# RAK3162_NRF54L15.net
KiCad netlist of a schematic drawn in Altium Designer
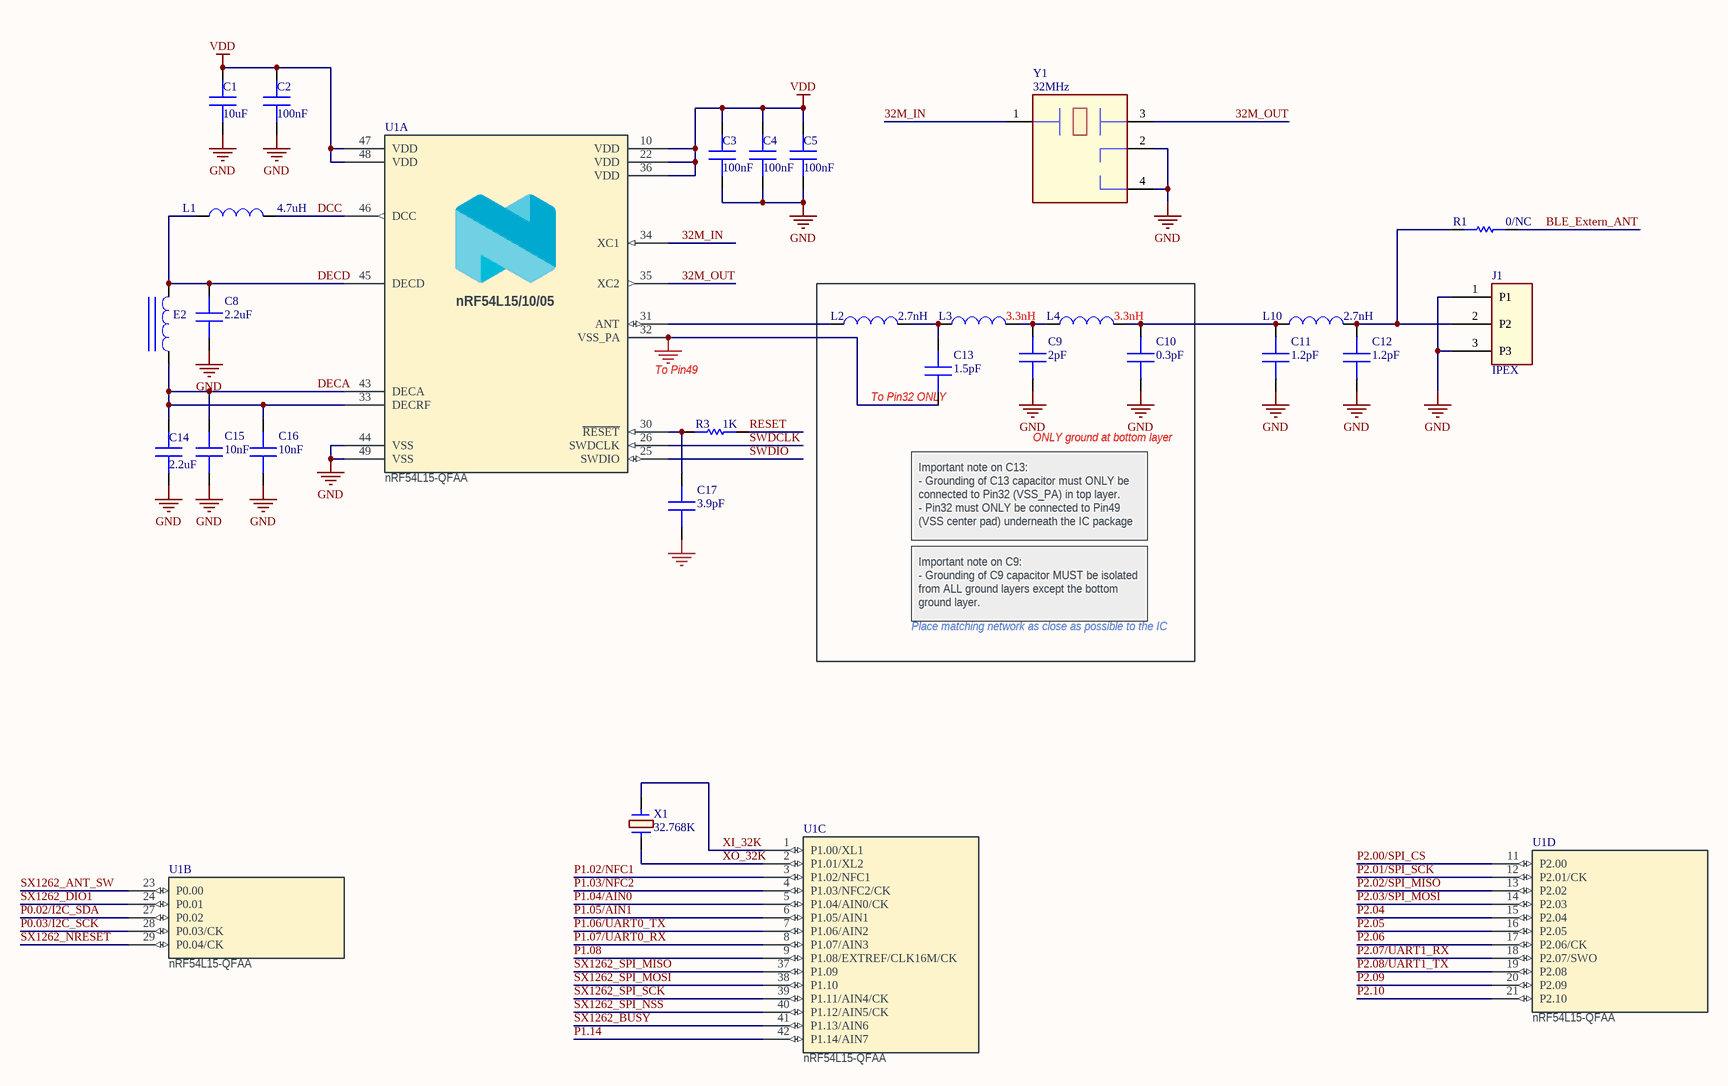
[diagram p0: RAK3162_NRF54L15.SchDoc]

(export (version "E")
  (design (tool "Eeschema 10.0.6"))
  (components
    (comp (ref "C1")
      (value "10uF")
      (footprint "sc0402")
      (description "Capacitor-10V-10uF-±20%-X5R-0402")
      (fields (field (name "MANUFACTURER") "YAGEO") (field (name "TOLERANCE") "±20%"))
      (libsource (lib "RAK_Database_Lib_2022") (part "CAPACITOR NP"))
    )
    (comp (ref "C2")
      (value "100nF")
      (footprint "sc0201")
      (description "Capacitor-6.3V-100nF-±10%-X5R-0201")
      (fields (field (name "MANUFACTURER") "YAGEO") (field (name "TOLERANCE") "±10%"))
      (libsource (lib "RAK_Database_Lib_2022") (part "CAPACITOR NP"))
    )
    (comp (ref "C3")
      (value "100nF")
      (footprint "sc0201")
      (description "Capacitor-6.3V-100nF-±10%-X5R-0201")
      (fields (field (name "MANUFACTURER") "YAGEO") (field (name "TOLERANCE") "±10%"))
      (libsource (lib "RAK_Database_Lib_2022") (part "CAPACITOR NP"))
    )
    (comp (ref "C4")
      (value "100nF")
      (footprint "sc0201")
      (description "Capacitor-6.3V-100nF-±10%-X5R-0201")
      (fields (field (name "MANUFACTURER") "YAGEO") (field (name "TOLERANCE") "±10%"))
      (libsource (lib "RAK_Database_Lib_2022") (part "CAPACITOR NP"))
    )
    (comp (ref "C5")
      (value "100nF")
      (footprint "sc0201")
      (description "Capacitor-6.3V-100nF-±10%-X5R-0201")
      (fields (field (name "MANUFACTURER") "YAGEO") (field (name "TOLERANCE") "±10%"))
      (libsource (lib "RAK_Database_Lib_2022") (part "CAPACITOR NP"))
    )
    (comp (ref "C8")
      (value "2.2uF")
      (footprint "sc0201")
      (description "Capacitor-6.3V-2.2uF-±20%-X5R-0201")
      (fields (field (name "MANUFACTURER") "YAGEO") (field (name "TOLERANCE") "±20%"))
      (libsource (lib "RAK_Database_Lib_2022") (part "CAPACITOR NP"))
    )
    (comp (ref "C9")
      (value "2pF")
      (footprint "sc0201")
      (description "Capacitor-50V-2pF-±0.1pF-COG-0201")
      (fields (field (name "MANUFACTURER") "深圳市宇阳科技发展有限公司") (field (name "TOLERANCE") "±0.1pF"))
      (libsource (lib "RAK_Database_Lib_2022") (part "CAPACITOR NP"))
    )
    (comp (ref "C10")
      (value "0.3pF")
      (footprint "sc0201")
      (description "Capacitor-50V-0.3pF-±0.1pF-NPO-0201")
      (fields (field (name "MANUFACTURER") "YAGEO") (field (name "TOLERANCE") "±0.1pF"))
      (libsource (lib "RAK_Database_Lib_2022") (part "CAPACITOR NP"))
    )
    (comp (ref "C11")
      (value "1.2pF")
      (footprint "sc0201")
      (description "Capacitor-50V-1.2pF-±0.1pF-COG-0201")
      (fields (field (name "MANUFACTURER") "MuRATA") (field (name "TOLERANCE") "±0.1pF"))
      (libsource (lib "RAK_Database_Lib_2022") (part "CAPACITOR NP"))
    )
    (comp (ref "C12")
      (value "1.2pF")
      (footprint "sc0201")
      (description "Capacitor-50V-1.2pF-±0.1pF-COG-0201")
      (fields (field (name "MANUFACTURER") "MuRATA") (field (name "TOLERANCE") "±0.1pF"))
      (libsource (lib "RAK_Database_Lib_2022") (part "CAPACITOR NP"))
    )
    (comp (ref "C13")
      (value "1.5pF")
      (footprint "sc0201")
      (description "Capacitor-50V-1.5pF-±0.25pF-COG-0201")
      (fields (field (name "MANUFACTURER") "YAGEO") (field (name "TOLERANCE") "±0.25pF"))
      (libsource (lib "RAK_Database_Lib_2022") (part "CAPACITOR NP"))
    )
    (comp (ref "C14")
      (value "2.2uF")
      (footprint "sc0201")
      (description "Capacitor-6.3V-2.2uF-±20%-X5R-0201")
      (fields (field (name "MANUFACTURER") "YAGEO") (field (name "TOLERANCE") "±20%"))
      (libsource (lib "RAK_Database_Lib_2022") (part "CAPACITOR NP"))
    )
    (comp (ref "C15")
      (value "10nF")
      (footprint "sc0201")
      (description "Capacitor-10V-10nF-±10%-X7R-0201")
      (fields (field (name "MANUFACTURER") "YAGEO") (field (name "TOLERANCE") "±10%"))
      (libsource (lib "RAK_Database_Lib_2022") (part "CAPACITOR NP"))
    )
    (comp (ref "C16")
      (value "10nF")
      (footprint "sc0201")
      (description "Capacitor-10V-10nF-±10%-X7R-0201")
      (fields (field (name "MANUFACTURER") "YAGEO") (field (name "TOLERANCE") "±10%"))
      (libsource (lib "RAK_Database_Lib_2022") (part "CAPACITOR NP"))
    )
    (comp (ref "C17")
      (value "3.9pF")
      (footprint "sc0201")
      (description "Capacitor-50V-3.9pF-±0.25pF-NPO-0201")
      (fields (field (name "MANUFACTURER") "YAGEO") (field (name "TOLERANCE") "±0.25pF"))
      (libsource (lib "RAK_Database_Lib_2022") (part "CAPACITOR NP"))
    )
    (comp (ref "E2")
      (value "BEAD")
      (footprint "SL0201")
      (description "EMI Ferrite Bead-240Ω±25%@100MHz-0.38Ω-350mA-0201")
      (fields (field (name "MANUFACTURER") "Murata") (field (name "PART NUMBER") "BLM03AX241SN1D"))
      (libsource (lib "RAK_Database_Lib_2022") (part "BEAD"))
    )
    (comp (ref "J1")
      (value "IPEX")
      (footprint "SCOXSMA_T")
      (description "Coaxial Connectors-IPEX MHF1-Receptacle, Male Pin-50Ohm-Surface Mount")
      (fields (field (name "MANUFACTURER") "BLDZ01") (field (name "PART_NUMBER") "ECT818000071"))
      (libsource (lib "RAK_Database_Lib_2022") (part "UFL"))
    )
    (comp (ref "L1")
      (value "4.7uH")
      (footprint "SL0603")
      (description "Power Inductor-4.7uH-±20%-0.5Ω-120mA-0603")
      (fields (field (name "MANUFACTURER") "TDK") (field (name "PART NUMBER") "MLZ1608M4R7WT000"))
      (libsource (lib "RAK_Database_Lib_2022") (part "INDUCTOR"))
    )
    (comp (ref "L2")
      (value "2.7nH")
      (footprint "sl0201")
      (description "Inductor-2.7nH-±0.1nH-0.2Ω-500mA-0201")
      (fields (field (name "MANUFACTURER") "MURATA") (field (name "PART NUMBER") "LQP03TN2N7B02D"))
      (libsource (lib "RAK_Database_Lib_2022") (part "INDUCTOR"))
    )
    (comp (ref "L3")
      (value "3.3nH")
      (footprint "sl0201")
      (description "Inductor-3.3nH-±0.1nH-0.25Ω-450mA-0201")
      (fields (field (name "MANUFACTURER") "MURATA") (field (name "PART NUMBER") "LQP03TN3N3B02"))
      (libsource (lib "RAK_Database_Lib_2022") (part "INDUCTOR"))
    )
    (comp (ref "L4")
      (value "3.3nH")
      (footprint "sl0201")
      (description "Inductor-3.3nH-±0.1nH-0.25Ω-450mA-0201")
      (fields (field (name "MANUFACTURER") "MURATA") (field (name "PART NUMBER") "LQP03TN3N3B02"))
      (libsource (lib "RAK_Database_Lib_2022") (part "INDUCTOR"))
    )
    (comp (ref "L10")
      (value "2.7nH")
      (footprint "sl0201")
      (description "Inductor-2.7nH-±0.1nH-0.2Ω-500mA-0201")
      (fields (field (name "MANUFACTURER") "MURATA") (field (name "PART NUMBER") "LQP03TN2N7B02D"))
      (libsource (lib "RAK_Database_Lib_2022") (part "INDUCTOR"))
    )
    (comp (ref "R1")
      (value "0/NC")
      (footprint "sr0201")
      (description "Resistor-0Ω-0.5A-50mΩMAX-0201")
      (fields (field (name "MANUFACTURER") "YAGEO") (field (name "PART NUMBER") "RC0201JR-070RL"))
      (libsource (lib "RAK_Database_Lib_2022") (part "RESISTOR"))
    )
    (comp (ref "R3")
      (value "1K")
      (footprint "sr0201")
      (description "Resistor-1/20W-1KΩ-±1%-0201")
      (fields (field (name "MANUFACTURER") "YAGEO") (field (name "PART NUMBER") "RC0201FR-071KL"))
      (libsource (lib "RAK_Database_Lib_2022") (part "RESISTOR"))
    )
    (comp (ref "U1")
      (value "nRF54L15-QFAA")
      (footprint "QFN40P600X600X90-48N")
      (fields (field (name "MANUFACTURER") "Nordic Semiconductor") (field (name "AUTHOR") "stl1"))
      (libsource (lib "RAK_Symbol_Library") (part "nRF54L15-QFAA"))
    )
    (comp (ref "X1")
      (value "32.768K")
      (footprint "CM212H")
      (description "Crystal-32.768KHz-12.5pF-±20ppm-−40~+85℃-SMD-2012-2pin")
      (fields (field (name "MANUFACTURER") "XTCS01") (field (name "PART NUMBER") "CM212H"))
      (libsource (lib "RAK_Database_Lib_2022") (part "CM212H"))
    )
    (comp (ref "Y1")
      (value "32MHz")
      (footprint "S0SC4-2016")
      (description "Crystal-32MHz-6pF-±20ppm-70Ω-SMD-2016-4pin")
      (fields (field (name "MANUFACTURER") "MURATA") (field (name "PART NUMBER") "XRCGB32M000F2P10R0"))
      (libsource (lib "RAK_Database_Lib_2022") (part "CRYSTAL_4P"))
    )
  )
  (nets
    (net (code "1") (name "/32M_IN") (class "Default")
      (node (ref "U1") (pin "34") (pinfunction "XC1_34") (pintype "input"))
      (node (ref "Y1") (pin "1") (pinfunction "H1_1") (pintype "passive"))
    )
    (net (code "2") (name "/32M_OUT") (class "Default")
      (node (ref "U1") (pin "35") (pinfunction "XC2_35") (pintype "output"))
      (node (ref "Y1") (pin "3") (pinfunction "H2_3") (pintype "passive"))
    )
    (net (code "3") (name "/BLE_Extern_ANT") (class "Default")
      (node (ref "R1") (pin "1") (pinfunction "1_1") (pintype "passive"))
    )
    (net (code "4") (name "/DCC") (class "Default")
      (node (ref "L1") (pin "2") (pinfunction "2_2") (pintype "passive"))
      (node (ref "U1") (pin "46") (pinfunction "DCC_46") (pintype "output"))
    )
    (net (code "5") (name "/DECA") (class "Default")
      (node (ref "C14") (pin "2") (pinfunction "NEG_2") (pintype "passive"))
      (node (ref "C15") (pin "2") (pinfunction "NEG_2") (pintype "passive"))
      (node (ref "C16") (pin "2") (pinfunction "NEG_2") (pintype "passive"))
      (node (ref "E2") (pin "1") (pinfunction "1_1") (pintype "passive"))
      (node (ref "U1") (pin "33") (pinfunction "DECRF_33") (pintype "power_in"))
      (node (ref "U1") (pin "43") (pinfunction "DECA_43") (pintype "power_in"))
    )
    (net (code "6") (name "/DECD") (class "Default")
      (node (ref "C8") (pin "2") (pinfunction "NEG_2") (pintype "passive"))
      (node (ref "E2") (pin "2") (pinfunction "2_2") (pintype "passive"))
      (node (ref "L1") (pin "1") (pinfunction "1_1") (pintype "passive"))
      (node (ref "U1") (pin "45") (pinfunction "DECD_45") (pintype "power_in"))
    )
    (net (code "7") (name "/P0.02{slash}I2C_SDA") (class "Default")
      (node (ref "U1") (pin "27") (pinfunction "P0.02_27") (pintype "bidirectional"))
    )
    (net (code "8") (name "/P0.03{slash}I2C_SCK") (class "Default")
      (node (ref "U1") (pin "28") (pinfunction "P0.03/CK_28") (pintype "bidirectional"))
    )
    (net (code "9") (name "/P1.02{slash}NFC1") (class "Default")
      (node (ref "U1") (pin "3") (pinfunction "P1.02/NFC1_3") (pintype "bidirectional"))
    )
    (net (code "10") (name "/P1.03{slash}NFC2") (class "Default")
      (node (ref "U1") (pin "4") (pinfunction "P1.03/NFC2/CK_4") (pintype "bidirectional"))
    )
    (net (code "11") (name "/P1.04{slash}AIN0") (class "Default")
      (node (ref "U1") (pin "5") (pinfunction "P1.04/AIN0/CK_5") (pintype "bidirectional"))
    )
    (net (code "12") (name "/P1.05{slash}AIN1") (class "Default")
      (node (ref "U1") (pin "6") (pinfunction "P1.05/AIN1_6") (pintype "bidirectional"))
    )
    (net (code "13") (name "/P1.06{slash}UART0_TX") (class "Default")
      (node (ref "U1") (pin "7") (pinfunction "P1.06/AIN2_7") (pintype "bidirectional"))
    )
    (net (code "14") (name "/P1.07{slash}UART0_RX") (class "Default")
      (node (ref "U1") (pin "8") (pinfunction "P1.07/AIN3_8") (pintype "bidirectional"))
    )
    (net (code "15") (name "/P1.08") (class "Default")
      (node (ref "U1") (pin "9") (pinfunction "P1.08/EXTREF/CLK16M/CK_9") (pintype "bidirectional"))
    )
    (net (code "16") (name "/P1.14") (class "Default")
      (node (ref "U1") (pin "42") (pinfunction "P1.14/AIN7_42") (pintype "bidirectional"))
    )
    (net (code "17") (name "/P2.00{slash}SPI_CS") (class "Default")
      (node (ref "U1") (pin "11") (pinfunction "P2.00_11") (pintype "bidirectional"))
    )
    (net (code "18") (name "/P2.01{slash}SPI_SCK") (class "Default")
      (node (ref "U1") (pin "12") (pinfunction "P2.01/CK_12") (pintype "bidirectional"))
    )
    (net (code "19") (name "/P2.02{slash}SPI_MISO") (class "Default")
      (node (ref "U1") (pin "13") (pinfunction "P2.02_13") (pintype "bidirectional"))
    )
    (net (code "20") (name "/P2.03{slash}SPI_MOSI") (class "Default")
      (node (ref "U1") (pin "14") (pinfunction "P2.03_14") (pintype "bidirectional"))
    )
    (net (code "21") (name "/P2.04") (class "Default")
      (node (ref "U1") (pin "15") (pinfunction "P2.04_15") (pintype "bidirectional"))
    )
    (net (code "22") (name "/P2.05") (class "Default")
      (node (ref "U1") (pin "16") (pinfunction "P2.05_16") (pintype "bidirectional"))
    )
    (net (code "23") (name "/P2.06") (class "Default")
      (node (ref "U1") (pin "17") (pinfunction "P2.06/CK_17") (pintype "bidirectional"))
    )
    (net (code "24") (name "/P2.07{slash}UART1_RX") (class "Default")
      (node (ref "U1") (pin "18") (pinfunction "P2.07/SWO_18") (pintype "bidirectional"))
    )
    (net (code "25") (name "/P2.08{slash}UART1_TX") (class "Default")
      (node (ref "U1") (pin "19") (pinfunction "P2.08_19") (pintype "bidirectional"))
    )
    (net (code "26") (name "/P2.09") (class "Default")
      (node (ref "U1") (pin "20") (pinfunction "P2.09_20") (pintype "bidirectional"))
    )
    (net (code "27") (name "/P2.10") (class "Default")
      (node (ref "U1") (pin "21") (pinfunction "P2.10_21") (pintype "bidirectional"))
    )
    (net (code "28") (name "/RESET") (class "Default")
      (node (ref "R3") (pin "1") (pinfunction "1_1") (pintype "passive"))
    )
    (net (code "29") (name "/SWDCLK") (class "Default")
      (node (ref "U1") (pin "26") (pinfunction "SWDCLK_26") (pintype "input"))
    )
    (net (code "30") (name "/SWDIO") (class "Default")
      (node (ref "U1") (pin "25") (pinfunction "SWDIO_25") (pintype "bidirectional"))
    )
    (net (code "31") (name "/SX1262_ANT_SW") (class "Default")
      (node (ref "U1") (pin "23") (pinfunction "P0.00_23") (pintype "bidirectional"))
    )
    (net (code "32") (name "/SX1262_BUSY") (class "Default")
      (node (ref "U1") (pin "41") (pinfunction "P1.13/AIN6_41") (pintype "bidirectional"))
    )
    (net (code "33") (name "/SX1262_DIO1") (class "Default")
      (node (ref "U1") (pin "24") (pinfunction "P0.01_24") (pintype "bidirectional"))
    )
    (net (code "34") (name "/SX1262_NRESET") (class "Default")
      (node (ref "U1") (pin "29") (pinfunction "P0.04/CK_29") (pintype "bidirectional"))
    )
    (net (code "35") (name "/SX1262_SPI_MISO") (class "Default")
      (node (ref "U1") (pin "37") (pinfunction "P1.09_37") (pintype "bidirectional"))
    )
    (net (code "36") (name "/SX1262_SPI_MOSI") (class "Default")
      (node (ref "U1") (pin "38") (pinfunction "P1.10_38") (pintype "bidirectional"))
    )
    (net (code "37") (name "/SX1262_SPI_NSS") (class "Default")
      (node (ref "U1") (pin "40") (pinfunction "P1.12/AIN5/CK_40") (pintype "bidirectional"))
    )
    (net (code "38") (name "/SX1262_SPI_SCK") (class "Default")
      (node (ref "U1") (pin "39") (pinfunction "P1.11/AIN4/CK_39") (pintype "bidirectional"))
    )
    (net (code "39") (name "/XI_32K") (class "Default")
      (node (ref "U1") (pin "1") (pinfunction "P1.00/XL1_1") (pintype "bidirectional"))
      (node (ref "X1") (pin "2") (pinfunction "2_2") (pintype "passive"))
    )
    (net (code "40") (name "/XO_32K") (class "Default")
      (node (ref "U1") (pin "2") (pinfunction "P1.01/XL2_2") (pintype "bidirectional"))
      (node (ref "X1") (pin "1") (pinfunction "1_1") (pintype "passive"))
    )
    (net (code "41") (name "GND") (class "Default")
      (node (ref "C1") (pin "1") (pinfunction "POS_1") (pintype "passive"))
      (node (ref "C10") (pin "1") (pinfunction "POS_1") (pintype "passive"))
      (node (ref "C11") (pin "1") (pinfunction "POS_1") (pintype "passive"))
      (node (ref "C12") (pin "1") (pinfunction "POS_1") (pintype "passive"))
      (node (ref "C13") (pin "1") (pinfunction "POS_1") (pintype "passive"))
      (node (ref "C14") (pin "1") (pinfunction "POS_1") (pintype "passive"))
      (node (ref "C15") (pin "1") (pinfunction "POS_1") (pintype "passive"))
      (node (ref "C16") (pin "1") (pinfunction "POS_1") (pintype "passive"))
      (node (ref "C17") (pin "1") (pinfunction "POS_1") (pintype "passive"))
      (node (ref "C2") (pin "1") (pinfunction "POS_1") (pintype "passive"))
      (node (ref "C3") (pin "1") (pinfunction "POS_1") (pintype "passive"))
      (node (ref "C4") (pin "1") (pinfunction "POS_1") (pintype "passive"))
      (node (ref "C5") (pin "1") (pinfunction "POS_1") (pintype "passive"))
      (node (ref "C8") (pin "1") (pinfunction "POS_1") (pintype "passive"))
      (node (ref "C9") (pin "1") (pinfunction "POS_1") (pintype "passive"))
      (node (ref "J1") (pin "1") (pinfunction "P1_1") (pintype "passive"))
      (node (ref "J1") (pin "3") (pinfunction "P3_3") (pintype "passive"))
      (node (ref "U1") (pin "32") (pinfunction "VSS_PA_32") (pintype "power_in"))
      (node (ref "U1") (pin "44") (pinfunction "VSS_44") (pintype "power_in"))
      (node (ref "U1") (pin "49") (pinfunction "VSS_49") (pintype "power_in"))
      (node (ref "Y1") (pin "2") (pinfunction "GND1_2") (pintype "power_in"))
      (node (ref "Y1") (pin "4") (pinfunction "GND2_4") (pintype "power_in"))
    )
    (net (code "42") (name "Net-(C9-NEG)") (class "Default")
      (node (ref "C9") (pin "2") (pinfunction "NEG_2") (pintype "passive"))
      (node (ref "L3") (pin "2") (pinfunction "2_2") (pintype "passive"))
      (node (ref "L4") (pin "1") (pinfunction "1_1") (pintype "passive"))
    )
    (net (code "43") (name "Net-(C10-NEG)") (class "Default")
      (node (ref "C10") (pin "2") (pinfunction "NEG_2") (pintype "passive"))
      (node (ref "C11") (pin "2") (pinfunction "NEG_2") (pintype "passive"))
      (node (ref "L10") (pin "1") (pinfunction "1_1") (pintype "passive"))
      (node (ref "L4") (pin "2") (pinfunction "2_2") (pintype "passive"))
    )
    (net (code "44") (name "Net-(C12-NEG)") (class "Default")
      (node (ref "C12") (pin "2") (pinfunction "NEG_2") (pintype "passive"))
      (node (ref "J1") (pin "2") (pinfunction "P2_2") (pintype "passive"))
      (node (ref "L10") (pin "2") (pinfunction "2_2") (pintype "passive"))
      (node (ref "R1") (pin "2") (pinfunction "2_2") (pintype "passive"))
    )
    (net (code "45") (name "Net-(C13-NEG)") (class "Default")
      (node (ref "C13") (pin "2") (pinfunction "NEG_2") (pintype "passive"))
      (node (ref "L2") (pin "2") (pinfunction "2_2") (pintype "passive"))
      (node (ref "L3") (pin "1") (pinfunction "1_1") (pintype "passive"))
    )
    (net (code "46") (name "Net-(C17-NEG)") (class "Default")
      (node (ref "C17") (pin "2") (pinfunction "NEG_2") (pintype "passive"))
      (node (ref "R3") (pin "2") (pinfunction "2_2") (pintype "passive"))
      (node (ref "U1") (pin "30") (pinfunction "~{RESET}_30") (pintype "input"))
    )
    (net (code "47") (name "Net-(U1A-ANT)") (class "Default")
      (node (ref "L2") (pin "1") (pinfunction "1_1") (pintype "passive"))
      (node (ref "U1") (pin "31") (pinfunction "ANT_31") (pintype "bidirectional"))
    )
    (net (code "48") (name "VDD") (class "Default")
      (node (ref "C1") (pin "2") (pinfunction "NEG_2") (pintype "passive"))
      (node (ref "C2") (pin "2") (pinfunction "NEG_2") (pintype "passive"))
      (node (ref "C3") (pin "2") (pinfunction "NEG_2") (pintype "passive"))
      (node (ref "C4") (pin "2") (pinfunction "NEG_2") (pintype "passive"))
      (node (ref "C5") (pin "2") (pinfunction "NEG_2") (pintype "passive"))
      (node (ref "U1") (pin "10") (pinfunction "VDD_10") (pintype "power_in"))
      (node (ref "U1") (pin "22") (pinfunction "VDD_22") (pintype "power_in"))
      (node (ref "U1") (pin "36") (pinfunction "VDD_36") (pintype "power_in"))
      (node (ref "U1") (pin "47") (pinfunction "VDD_47") (pintype "power_in"))
      (node (ref "U1") (pin "48") (pinfunction "VDD_48") (pintype "power_in"))
    )
  )
)
